# HumidityMetter.net
KiCad netlist of a schematic drawn in EAGLE
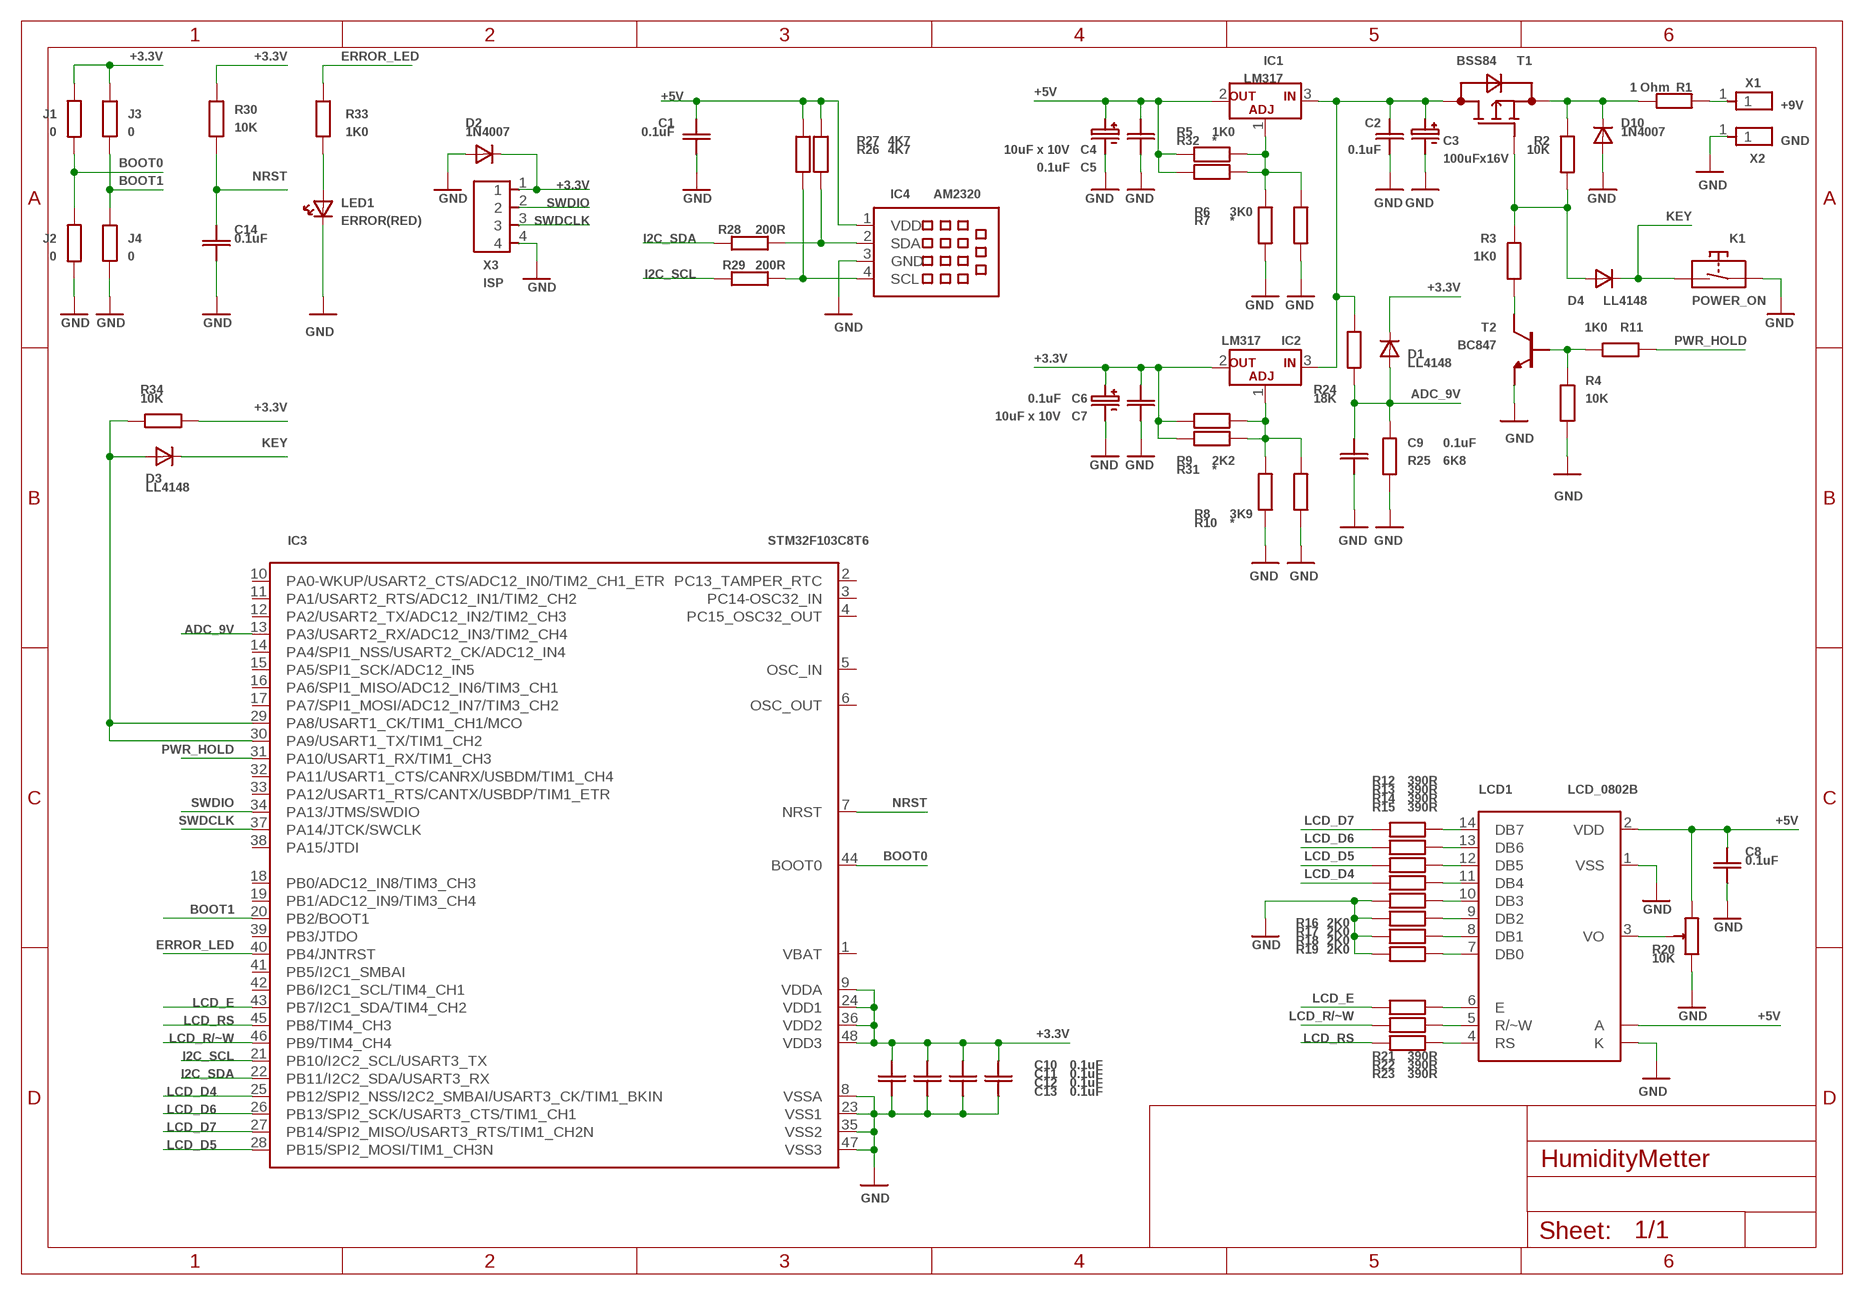
[diagram p0: schematic, sheet 1]

(export (version "E")
  (design (tool "Eeschema 10.0.6"))
  (components
    (comp (ref "C1")
      (value "0.1uF")
      (footprint "eagle-import:RSMD_0805")
      (libsource (lib "eagle-import") (part "CSMD_0805"))
    )
    (comp (ref "C2")
      (value "0.1uF")
      (footprint "eagle-import:RSMD_0805")
      (libsource (lib "eagle-import") (part "CSMD_0805"))
    )
    (comp (ref "C3")
      (value "100uFx16V")
      (footprint "eagle-import:CE_6.3MM")
      (libsource (lib "eagle-import") (part "CE6.3MM"))
    )
    (comp (ref "C4")
      (value "10uF x 10V")
      (footprint "eagle-import:CE_5.2MM")
      (libsource (lib "eagle-import") (part "CE5.2MM"))
    )
    (comp (ref "C5")
      (value "0.1uF")
      (footprint "eagle-import:RSMD_0805")
      (libsource (lib "eagle-import") (part "CSMD_0805"))
    )
    (comp (ref "C6")
      (value "0.1uF")
      (footprint "eagle-import:RSMD_0805")
      (libsource (lib "eagle-import") (part "CSMD_0805"))
    )
    (comp (ref "C7")
      (value "10uF x 10V")
      (footprint "eagle-import:CE_5.2MM")
      (libsource (lib "eagle-import") (part "CE5.2MM"))
    )
    (comp (ref "C8")
      (value "0.1uF")
      (footprint "eagle-import:RSMD_0805")
      (libsource (lib "eagle-import") (part "CSMD_0805"))
    )
    (comp (ref "C9")
      (value "0.1uF")
      (footprint "eagle-import:RSMD_0805")
      (libsource (lib "eagle-import") (part "CSMD_0805"))
    )
    (comp (ref "C10")
      (value "0.1uF")
      (footprint "eagle-import:RSMD_0805")
      (libsource (lib "eagle-import") (part "CSMD_0805"))
    )
    (comp (ref "C11")
      (value "0.1uF")
      (footprint "eagle-import:RSMD_0805")
      (libsource (lib "eagle-import") (part "CSMD_0805"))
    )
    (comp (ref "C12")
      (value "0.1uF")
      (footprint "eagle-import:RSMD_0805")
      (libsource (lib "eagle-import") (part "CSMD_0805"))
    )
    (comp (ref "C13")
      (value "0.1uF")
      (footprint "eagle-import:RSMD_0805")
      (libsource (lib "eagle-import") (part "CSMD_0805"))
    )
    (comp (ref "C14")
      (value "0.1uF")
      (footprint "eagle-import:RSMD_0805")
      (libsource (lib "eagle-import") (part "CSMD_0805"))
    )
    (comp (ref "D1")
      (value "LL4148")
      (footprint "eagle-import:SOD-80")
      (libsource (lib "eagle-import") (part "LL4147SOD-80"))
    )
    (comp (ref "D2")
      (value "1N4007")
      (footprint "eagle-import:DO-41_10MM")
      (libsource (lib "eagle-import") (part "1N4001DO-41_10MM"))
    )
    (comp (ref "D3")
      (value "LL4148")
      (footprint "eagle-import:SOD-80")
      (libsource (lib "eagle-import") (part "LL4147SOD-80"))
    )
    (comp (ref "D4")
      (value "LL4148")
      (footprint "eagle-import:SOD-80")
      (libsource (lib "eagle-import") (part "LL4147SOD-80"))
    )
    (comp (ref "D10")
      (value "1N4007")
      (footprint "eagle-import:DO-41_10MM")
      (libsource (lib "eagle-import") (part "1N4001DO-41_10MM"))
    )
    (comp (ref "IC1")
      (value "LM317")
      (footprint "eagle-import:D2PAK")
      (libsource (lib "eagle-import") (part "LM317(D2PAK)"))
    )
    (comp (ref "IC2")
      (value "LM317")
      (footprint "eagle-import:D2PAK")
      (libsource (lib "eagle-import") (part "LM317(D2PAK)"))
    )
    (comp (ref "IC3")
      (value "STM32F103C8T6")
      (footprint "eagle-import:LQFP48")
      (libsource (lib "eagle-import") (part "STM32F103C8T6(LQFP48)(LQFP48)"))
    )
    (comp (ref "IC4")
      (value "AM2320")
      (footprint "eagle-import:AM2320_HOR")
      (libsource (lib "eagle-import") (part "AM2320(HOR)"))
    )
    (comp (ref "J1")
      (value "0")
      (footprint "eagle-import:RSMD_0805")
      (libsource (lib "eagle-import") (part "RSMD_0805"))
    )
    (comp (ref "J2")
      (value "0")
      (footprint "eagle-import:RSMD_0805")
      (libsource (lib "eagle-import") (part "RSMD_0805"))
    )
    (comp (ref "J3")
      (value "0")
      (footprint "eagle-import:RSMD_0805")
      (libsource (lib "eagle-import") (part "RSMD_0805"))
    )
    (comp (ref "J4")
      (value "0")
      (footprint "eagle-import:RSMD_0805")
      (libsource (lib "eagle-import") (part "RSMD_0805"))
    )
    (comp (ref "K1")
      (value "POWER_ON")
      (footprint "eagle-import:KEY_7X4.5")
      (libsource (lib "eagle-import") (part "KEY(7X4.5)"))
    )
    (comp (ref "LCD1")
      (value "LCD_0802B")
      (footprint "eagle-import:LCD_0802B(CHINA_CLONE)")
      (libsource (lib "eagle-import") (part "LCD_0802B(0802B_CHINA_CLONE)"))
    )
    (comp (ref "LED1")
      (value "ERROR(RED)")
      (footprint "eagle-import:LED_0805")
      (libsource (lib "eagle-import") (part "LED3MM(SMD0805)"))
    )
    (comp (ref "R1")
      (value "1 Ohm")
      (footprint "eagle-import:R0207")
      (libsource (lib "eagle-import") (part "R0207"))
    )
    (comp (ref "R2")
      (value "10K")
      (footprint "eagle-import:RSMD_0805")
      (libsource (lib "eagle-import") (part "RSMD_0805"))
    )
    (comp (ref "R3")
      (value "1K0")
      (footprint "eagle-import:RSMD_0805")
      (libsource (lib "eagle-import") (part "RSMD_0805"))
    )
    (comp (ref "R4")
      (value "10K")
      (footprint "eagle-import:RSMD_0805")
      (libsource (lib "eagle-import") (part "RSMD_0805"))
    )
    (comp (ref "R5")
      (value "1K0")
      (footprint "eagle-import:RSMD_0805")
      (libsource (lib "eagle-import") (part "RSMD_0805"))
    )
    (comp (ref "R6")
      (value "3K0")
      (footprint "eagle-import:RSMD_0805")
      (libsource (lib "eagle-import") (part "RSMD_0805"))
    )
    (comp (ref "R7")
      (value "*")
      (footprint "eagle-import:RSMD_0805")
      (libsource (lib "eagle-import") (part "RSMD_0805"))
    )
    (comp (ref "R8")
      (value "3K9")
      (footprint "eagle-import:RSMD_0805")
      (libsource (lib "eagle-import") (part "RSMD_0805"))
    )
    (comp (ref "R9")
      (value "2K2")
      (footprint "eagle-import:RSMD_0805")
      (libsource (lib "eagle-import") (part "RSMD_0805"))
    )
    (comp (ref "R10")
      (value "*")
      (footprint "eagle-import:RSMD_0805")
      (libsource (lib "eagle-import") (part "RSMD_0805"))
    )
    (comp (ref "R11")
      (value "1K0")
      (footprint "eagle-import:RSMD_1206_BIG_GAP")
      (libsource (lib "eagle-import") (part "RSMD_1206_BIG_GAP"))
    )
    (comp (ref "R12")
      (value "390R")
      (footprint "eagle-import:RSMD_0805")
      (libsource (lib "eagle-import") (part "RSMD_0805"))
    )
    (comp (ref "R13")
      (value "390R")
      (footprint "eagle-import:RSMD_0805")
      (libsource (lib "eagle-import") (part "RSMD_0805"))
    )
    (comp (ref "R14")
      (value "390R")
      (footprint "eagle-import:RSMD_0805")
      (libsource (lib "eagle-import") (part "RSMD_0805"))
    )
    (comp (ref "R15")
      (value "390R")
      (footprint "eagle-import:RSMD_0805")
      (libsource (lib "eagle-import") (part "RSMD_0805"))
    )
    (comp (ref "R16")
      (value "2K0")
      (footprint "eagle-import:RSMD_0805")
      (libsource (lib "eagle-import") (part "RSMD_0805"))
    )
    (comp (ref "R17")
      (value "2K0")
      (footprint "eagle-import:RSMD_0805")
      (libsource (lib "eagle-import") (part "RSMD_0805"))
    )
    (comp (ref "R18")
      (value "2K0")
      (footprint "eagle-import:RSMD_0805")
      (libsource (lib "eagle-import") (part "RSMD_0805"))
    )
    (comp (ref "R19")
      (value "2K0")
      (footprint "eagle-import:RSMD_0805")
      (libsource (lib "eagle-import") (part "RSMD_0805"))
    )
    (comp (ref "R20")
      (value "10K")
      (footprint "eagle-import:R_ADJ_STAND")
      (libsource (lib "eagle-import") (part "R_ADJSTAND_6.5_X_3.5MM"))
    )
    (comp (ref "R21")
      (value "390R")
      (footprint "eagle-import:RSMD_0805")
      (libsource (lib "eagle-import") (part "RSMD_0805"))
    )
    (comp (ref "R22")
      (value "390R")
      (footprint "eagle-import:RSMD_0805")
      (libsource (lib "eagle-import") (part "RSMD_0805"))
    )
    (comp (ref "R23")
      (value "390R")
      (footprint "eagle-import:RSMD_0805")
      (libsource (lib "eagle-import") (part "RSMD_0805"))
    )
    (comp (ref "R24")
      (value "18K")
      (footprint "eagle-import:RSMD_1206_BIG_GAP")
      (libsource (lib "eagle-import") (part "RSMD_1206_BIG_GAP"))
    )
    (comp (ref "R25")
      (value "6K8")
      (footprint "eagle-import:RSMD_0805")
      (libsource (lib "eagle-import") (part "RSMD_0805"))
    )
    (comp (ref "R26")
      (value "4K7")
      (footprint "eagle-import:R0207")
      (libsource (lib "eagle-import") (part "R0207"))
    )
    (comp (ref "R27")
      (value "4K7")
      (footprint "eagle-import:R0207")
      (libsource (lib "eagle-import") (part "R0207"))
    )
    (comp (ref "R28")
      (value "200R")
      (footprint "eagle-import:R0207")
      (libsource (lib "eagle-import") (part "R0207"))
    )
    (comp (ref "R29")
      (value "200R")
      (footprint "eagle-import:R0207")
      (libsource (lib "eagle-import") (part "R0207"))
    )
    (comp (ref "R30")
      (value "10K")
      (footprint "eagle-import:RSMD_0805")
      (libsource (lib "eagle-import") (part "RSMD_0805"))
    )
    (comp (ref "R31")
      (value "*")
      (footprint "eagle-import:RSMD_0805")
      (libsource (lib "eagle-import") (part "RSMD_0805"))
    )
    (comp (ref "R32")
      (value "*")
      (footprint "eagle-import:RSMD_0805")
      (libsource (lib "eagle-import") (part "RSMD_0805"))
    )
    (comp (ref "R33")
      (value "1K0")
      (footprint "eagle-import:RSMD_0805")
      (libsource (lib "eagle-import") (part "RSMD_0805"))
    )
    (comp (ref "R34")
      (value "10K")
      (footprint "eagle-import:RSMD_0805")
      (libsource (lib "eagle-import") (part "RSMD_0805"))
    )
    (comp (ref "T1")
      (value "BSS84")
      (footprint "eagle-import:SOT23")
      (libsource (lib "eagle-import") (part "BSS84(SOT23)"))
    )
    (comp (ref "T2")
      (value "BC847")
      (footprint "eagle-import:SOT23_SMALL_PADS")
      (libsource (lib "eagle-import") (part "BC847SOT23_SMALL_PADS"))
    )
    (comp (ref "X1")
      (value "+9V")
      (footprint "eagle-import:PIN1X1_D3.5MM")
      (libsource (lib "eagle-import") (part "PIN1X13.5MM_DRILL"))
    )
    (comp (ref "X2")
      (value "GND")
      (footprint "eagle-import:PIN1X1_D3.5MM")
      (libsource (lib "eagle-import") (part "PIN1X13.5MM_DRILL"))
    )
    (comp (ref "X3")
      (value "ISP")
      (footprint "eagle-import:PIN4X1_2.54MM")
      (libsource (lib "eagle-import") (part "PIN4X1(2.54MM)"))
    )
  )
  (nets
    (net (code "1") (name "/+3.3V") (class "Default")
      (node (ref "C10") (pin "PAD_1") (pinfunction "PIN1_PAD_1") (pintype "bidirectional"))
      (node (ref "C11") (pin "PAD_1") (pinfunction "PIN1_PAD_1") (pintype "bidirectional"))
      (node (ref "C12") (pin "PAD_1") (pinfunction "PIN1_PAD_1") (pintype "bidirectional"))
      (node (ref "C13") (pin "PAD_1") (pinfunction "PIN1_PAD_1") (pintype "bidirectional"))
      (node (ref "C6") (pin "PAD_1") (pinfunction "PIN1_PAD_1") (pintype "bidirectional"))
      (node (ref "C7") (pin "PLUS") (pinfunction "PLUS_PLUS") (pintype "bidirectional"))
      (node (ref "D1") (pin "CATHODE") (pinfunction "CATHODE_CATHODE") (pintype "passive"))
      (node (ref "D2") (pin "CATHODE") (pinfunction "CATHODE_CATHODE") (pintype "passive"))
      (node (ref "IC2") (pin "2") (pinfunction "OUT_2") (pintype "output"))
      (node (ref "IC3") (pin "24") (pinfunction "VDD1_24") (pintype "bidirectional"))
      (node (ref "IC3") (pin "36") (pinfunction "VDD2_36") (pintype "bidirectional"))
      (node (ref "IC3") (pin "48") (pinfunction "VDD3_48") (pintype "bidirectional"))
      (node (ref "IC3") (pin "9") (pinfunction "VDDA_9") (pintype "bidirectional"))
      (node (ref "J1") (pin "PAD_0") (pinfunction "PIN0_PAD_0") (pintype "passive"))
      (node (ref "J3") (pin "PAD_0") (pinfunction "PIN0_PAD_0") (pintype "passive"))
      (node (ref "R30") (pin "PAD_0") (pinfunction "PIN0_PAD_0") (pintype "passive"))
      (node (ref "R31") (pin "PAD_1") (pinfunction "PIN1_PAD_1") (pintype "passive"))
      (node (ref "R34") (pin "PAD_1") (pinfunction "PIN1_PAD_1") (pintype "passive"))
      (node (ref "R9") (pin "PAD_1") (pinfunction "PIN1_PAD_1") (pintype "passive"))
      (node (ref "X3") (pin "1") (pinfunction "1_1") (pintype "bidirectional"))
    )
    (net (code "2") (name "/+5V") (class "Default")
      (node (ref "C1") (pin "PAD_1") (pinfunction "PIN1_PAD_1") (pintype "bidirectional"))
      (node (ref "C4") (pin "PLUS") (pinfunction "PLUS_PLUS") (pintype "bidirectional"))
      (node (ref "C5") (pin "PAD_1") (pinfunction "PIN1_PAD_1") (pintype "bidirectional"))
      (node (ref "C8") (pin "PAD_1") (pinfunction "PIN1_PAD_1") (pintype "bidirectional"))
      (node (ref "IC1") (pin "2") (pinfunction "OUT_2") (pintype "output"))
      (node (ref "IC4") (pin "1") (pinfunction "VDD_1") (pintype "bidirectional"))
      (node (ref "LCD1") (pin "2") (pinfunction "VDD_2") (pintype "bidirectional"))
      (node (ref "LCD1") (pin "A") (pinfunction "A_A") (pintype "bidirectional"))
      (node (ref "R20") (pin "3") (pinfunction "END_B_3") (pintype "passive"))
      (node (ref "R26") (pin "PAD_0") (pinfunction "PIN0_PAD_0") (pintype "passive"))
      (node (ref "R27") (pin "PAD_0") (pinfunction "PIN0_PAD_0") (pintype "passive"))
      (node (ref "R32") (pin "PAD_1") (pinfunction "PIN1_PAD_1") (pintype "passive"))
      (node (ref "R5") (pin "PAD_1") (pinfunction "PIN1_PAD_1") (pintype "passive"))
    )
    (net (code "3") (name "/ADC_9V") (class "Default")
      (node (ref "C9") (pin "PAD_1") (pinfunction "PIN1_PAD_1") (pintype "bidirectional"))
      (node (ref "D1") (pin "ANODE") (pinfunction "ANODE_ANODE") (pintype "passive"))
      (node (ref "IC3") (pin "13") (pinfunction "PA3/USART2_RX/ADC12_IN3/TIM2_CH4_13") (pintype "bidirectional"))
      (node (ref "R24") (pin "PAD_1") (pinfunction "PIN1_PAD_1") (pintype "passive"))
      (node (ref "R25") (pin "PAD_0") (pinfunction "PIN0_PAD_0") (pintype "passive"))
    )
    (net (code "4") (name "/BOOT0") (class "Default")
      (node (ref "IC3") (pin "44") (pinfunction "BOOT0_44") (pintype "bidirectional"))
      (node (ref "J1") (pin "PAD_1") (pinfunction "PIN1_PAD_1") (pintype "passive"))
      (node (ref "J2") (pin "PAD_0") (pinfunction "PIN0_PAD_0") (pintype "passive"))
    )
    (net (code "5") (name "/BOOT1") (class "Default")
      (node (ref "IC3") (pin "20") (pinfunction "PB2/BOOT1_20") (pintype "bidirectional"))
      (node (ref "J3") (pin "PAD_1") (pinfunction "PIN1_PAD_1") (pintype "passive"))
      (node (ref "J4") (pin "PAD_0") (pinfunction "PIN0_PAD_0") (pintype "passive"))
    )
    (net (code "6") (name "/ERROR_LED") (class "Default")
      (node (ref "IC3") (pin "40") (pinfunction "PB4/JNTRST_40") (pintype "bidirectional"))
      (node (ref "R33") (pin "PAD_0") (pinfunction "PIN0_PAD_0") (pintype "passive"))
    )
    (net (code "7") (name "/I2C_SCL") (class "Default")
      (node (ref "IC3") (pin "21") (pinfunction "PB10/I2C2_SCL/USART3_TX_21") (pintype "bidirectional"))
      (node (ref "R29") (pin "PAD_0") (pinfunction "PIN0_PAD_0") (pintype "passive"))
    )
    (net (code "8") (name "/I2C_SDA") (class "Default")
      (node (ref "IC3") (pin "22") (pinfunction "PB11/I2C2_SDA/USART3_RX_22") (pintype "bidirectional"))
      (node (ref "R28") (pin "PAD_0") (pinfunction "PIN0_PAD_0") (pintype "passive"))
    )
    (net (code "9") (name "/KEY") (class "Default")
      (node (ref "D3") (pin "CATHODE") (pinfunction "CATHODE_CATHODE") (pintype "passive"))
      (node (ref "D4") (pin "CATHODE") (pinfunction "CATHODE_CATHODE") (pintype "passive"))
      (node (ref "K1") (pin "3") (pinfunction "2_3") (pintype "bidirectional"))
      (node (ref "K1") (pin "4") (pinfunction "2_4") (pintype "bidirectional"))
    )
    (net (code "10") (name "/LCD_D4") (class "Default")
      (node (ref "IC3") (pin "25") (pinfunction "PB12/SPI2_NSS/I2C2_SMBAI/USART3_CK/TIM1_BKIN_25") (pintype "bidirectional"))
      (node (ref "R15") (pin "PAD_1") (pinfunction "PIN1_PAD_1") (pintype "passive"))
    )
    (net (code "11") (name "/LCD_D5") (class "Default")
      (node (ref "IC3") (pin "28") (pinfunction "PB15/SPI2_MOSI/TIM1_CH3N_28") (pintype "bidirectional"))
      (node (ref "R14") (pin "PAD_1") (pinfunction "PIN1_PAD_1") (pintype "passive"))
    )
    (net (code "12") (name "/LCD_D6") (class "Default")
      (node (ref "IC3") (pin "26") (pinfunction "PB13/SPI2_SCK/USART3_CTS/TIM1_CH1_26") (pintype "bidirectional"))
      (node (ref "R13") (pin "PAD_1") (pinfunction "PIN1_PAD_1") (pintype "passive"))
    )
    (net (code "13") (name "/LCD_D7") (class "Default")
      (node (ref "IC3") (pin "27") (pinfunction "PB14/SPI2_MISO/USART3_RTS/TIM1_CH2N_27") (pintype "bidirectional"))
      (node (ref "R12") (pin "PAD_1") (pinfunction "PIN1_PAD_1") (pintype "passive"))
    )
    (net (code "14") (name "/LCD_E") (class "Default")
      (node (ref "IC3") (pin "43") (pinfunction "PB7/I2C1_SDA/TIM4_CH2_43") (pintype "bidirectional"))
      (node (ref "R21") (pin "PAD_1") (pinfunction "PIN1_PAD_1") (pintype "passive"))
    )
    (net (code "15") (name "/LCD_RS") (class "Default")
      (node (ref "IC3") (pin "45") (pinfunction "PB8/TIM4_CH3_45") (pintype "bidirectional"))
      (node (ref "R23") (pin "PAD_1") (pinfunction "PIN1_PAD_1") (pintype "passive"))
    )
    (net (code "16") (name "/LCD_R{slash}~{W}") (class "Default")
      (node (ref "IC3") (pin "46") (pinfunction "PB9/TIM4_CH4_46") (pintype "bidirectional"))
      (node (ref "R22") (pin "PAD_1") (pinfunction "PIN1_PAD_1") (pintype "passive"))
    )
    (net (code "17") (name "/NRST") (class "Default")
      (node (ref "C14") (pin "PAD_1") (pinfunction "PIN1_PAD_1") (pintype "bidirectional"))
      (node (ref "IC3") (pin "7") (pinfunction "NRST_7") (pintype "bidirectional"))
      (node (ref "R30") (pin "PAD_1") (pinfunction "PIN1_PAD_1") (pintype "passive"))
    )
    (net (code "18") (name "/PWR_HOLD") (class "Default")
      (node (ref "IC3") (pin "31") (pinfunction "PA10/USART1_RX/TIM1_CH3_31") (pintype "bidirectional"))
      (node (ref "R11") (pin "PAD_0") (pinfunction "PIN0_PAD_0") (pintype "passive"))
    )
    (net (code "19") (name "/SWDCLK") (class "Default")
      (node (ref "IC3") (pin "37") (pinfunction "PA14/JTCK/SWCLK_37") (pintype "bidirectional"))
      (node (ref "X3") (pin "3") (pinfunction "3_3") (pintype "bidirectional"))
    )
    (net (code "20") (name "/SWDIO") (class "Default")
      (node (ref "IC3") (pin "34") (pinfunction "PA13/JTMS/SWDIO_34") (pintype "bidirectional"))
      (node (ref "X3") (pin "2") (pinfunction "2_2") (pintype "bidirectional"))
    )
    (net (code "21") (name "GND") (class "Default")
      (node (ref "C1") (pin "PAD_0") (pinfunction "PIN0_PAD_0") (pintype "bidirectional"))
      (node (ref "C10") (pin "PAD_0") (pinfunction "PIN0_PAD_0") (pintype "bidirectional"))
      (node (ref "C11") (pin "PAD_0") (pinfunction "PIN0_PAD_0") (pintype "bidirectional"))
      (node (ref "C12") (pin "PAD_0") (pinfunction "PIN0_PAD_0") (pintype "bidirectional"))
      (node (ref "C13") (pin "PAD_0") (pinfunction "PIN0_PAD_0") (pintype "bidirectional"))
      (node (ref "C14") (pin "PAD_0") (pinfunction "PIN0_PAD_0") (pintype "bidirectional"))
      (node (ref "C2") (pin "PAD_0") (pinfunction "PIN0_PAD_0") (pintype "bidirectional"))
      (node (ref "C3") (pin "MINUS") (pinfunction "MINUS_MINUS") (pintype "bidirectional"))
      (node (ref "C4") (pin "MINUS") (pinfunction "MINUS_MINUS") (pintype "bidirectional"))
      (node (ref "C5") (pin "PAD_0") (pinfunction "PIN0_PAD_0") (pintype "bidirectional"))
      (node (ref "C6") (pin "PAD_0") (pinfunction "PIN0_PAD_0") (pintype "bidirectional"))
      (node (ref "C7") (pin "MINUS") (pinfunction "MINUS_MINUS") (pintype "bidirectional"))
      (node (ref "C8") (pin "PAD_0") (pinfunction "PIN0_PAD_0") (pintype "bidirectional"))
      (node (ref "C9") (pin "PAD_0") (pinfunction "PIN0_PAD_0") (pintype "bidirectional"))
      (node (ref "D10") (pin "ANODE") (pinfunction "ANODE_ANODE") (pintype "passive"))
      (node (ref "D2") (pin "ANODE") (pinfunction "ANODE_ANODE") (pintype "passive"))
      (node (ref "IC3") (pin "23") (pinfunction "VSS1_23") (pintype "bidirectional"))
      (node (ref "IC3") (pin "35") (pinfunction "VSS2_35") (pintype "bidirectional"))
      (node (ref "IC3") (pin "47") (pinfunction "VSS3_47") (pintype "bidirectional"))
      (node (ref "IC3") (pin "8") (pinfunction "VSSA_8") (pintype "bidirectional"))
      (node (ref "IC4") (pin "3") (pinfunction "GND_3") (pintype "bidirectional"))
      (node (ref "J2") (pin "PAD_1") (pinfunction "PIN1_PAD_1") (pintype "passive"))
      (node (ref "J4") (pin "PAD_1") (pinfunction "PIN1_PAD_1") (pintype "passive"))
      (node (ref "K1") (pin "1") (pinfunction "1_1") (pintype "bidirectional"))
      (node (ref "K1") (pin "2") (pinfunction "1_2") (pintype "bidirectional"))
      (node (ref "LCD1") (pin "1") (pinfunction "VSS_1") (pintype "bidirectional"))
      (node (ref "LCD1") (pin "K") (pinfunction "K_K") (pintype "bidirectional"))
      (node (ref "LED1") (pin "CATHODE") (pinfunction "CATHODE_CATHODE") (pintype "passive"))
      (node (ref "R10") (pin "PAD_1") (pinfunction "PIN1_PAD_1") (pintype "passive"))
      (node (ref "R16") (pin "PAD_1") (pinfunction "PIN1_PAD_1") (pintype "passive"))
      (node (ref "R17") (pin "PAD_1") (pinfunction "PIN1_PAD_1") (pintype "passive"))
      (node (ref "R18") (pin "PAD_1") (pinfunction "PIN1_PAD_1") (pintype "passive"))
      (node (ref "R19") (pin "PAD_1") (pinfunction "PIN1_PAD_1") (pintype "passive"))
      (node (ref "R20") (pin "1") (pinfunction "END_A_1") (pintype "passive"))
      (node (ref "R25") (pin "PAD_1") (pinfunction "PIN1_PAD_1") (pintype "passive"))
      (node (ref "R4") (pin "PAD_1") (pinfunction "PIN1_PAD_1") (pintype "passive"))
      (node (ref "R6") (pin "PAD_1") (pinfunction "PIN1_PAD_1") (pintype "passive"))
      (node (ref "R7") (pin "PAD_1") (pinfunction "PIN1_PAD_1") (pintype "passive"))
      (node (ref "R8") (pin "PAD_1") (pinfunction "PIN1_PAD_1") (pintype "passive"))
      (node (ref "T2") (pin "2") (pinfunction "E_2") (pintype "bidirectional"))
      (node (ref "X2") (pin "1") (pinfunction "1_1") (pintype "bidirectional"))
      (node (ref "X3") (pin "4") (pinfunction "4_4") (pintype "bidirectional"))
    )
    (net (code "22") (name "Net-(C2-PIN1)") (class "Default")
      (node (ref "C2") (pin "PAD_1") (pinfunction "PIN1_PAD_1") (pintype "bidirectional"))
      (node (ref "C3") (pin "PLUS") (pinfunction "PLUS_PLUS") (pintype "bidirectional"))
      (node (ref "IC1") (pin "3") (pinfunction "IN_3") (pintype "input"))
      (node (ref "IC2") (pin "3") (pinfunction "IN_3") (pintype "input"))
      (node (ref "R24") (pin "PAD_0") (pinfunction "PIN0_PAD_0") (pintype "passive"))
      (node (ref "T1") (pin "3") (pinfunction "DRAIN_3") (pintype "bidirectional"))
    )
    (net (code "23") (name "Net-(IC1-ADJ)") (class "Default")
      (node (ref "IC1") (pin "1") (pinfunction "ADJ_1") (pintype "input"))
      (node (ref "R32") (pin "PAD_0") (pinfunction "PIN0_PAD_0") (pintype "passive"))
      (node (ref "R5") (pin "PAD_0") (pinfunction "PIN0_PAD_0") (pintype "passive"))
      (node (ref "R6") (pin "PAD_0") (pinfunction "PIN0_PAD_0") (pintype "passive"))
      (node (ref "R7") (pin "PAD_0") (pinfunction "PIN0_PAD_0") (pintype "passive"))
    )
    (net (code "24") (name "Net-(IC2-ADJ)") (class "Default")
      (node (ref "IC2") (pin "1") (pinfunction "ADJ_1") (pintype "input"))
      (node (ref "R10") (pin "PAD_0") (pinfunction "PIN0_PAD_0") (pintype "passive"))
      (node (ref "R31") (pin "PAD_0") (pinfunction "PIN0_PAD_0") (pintype "passive"))
      (node (ref "R8") (pin "PAD_0") (pinfunction "PIN0_PAD_0") (pintype "passive"))
      (node (ref "R9") (pin "PAD_0") (pinfunction "PIN0_PAD_0") (pintype "passive"))
    )
    (net (code "25") (name "Net-(IC3-PA8{slash}USART1_CK{slash}TIM1_CH1{slash}MCO)") (class "Default")
      (node (ref "D3") (pin "ANODE") (pinfunction "ANODE_ANODE") (pintype "passive"))
      (node (ref "IC3") (pin "29") (pinfunction "PA8/USART1_CK/TIM1_CH1/MCO_29") (pintype "bidirectional"))
      (node (ref "IC3") (pin "30") (pinfunction "PA9/USART1_TX/TIM1_CH2_30") (pintype "bidirectional"))
      (node (ref "R34") (pin "PAD_0") (pinfunction "PIN0_PAD_0") (pintype "passive"))
    )
    (net (code "26") (name "Net-(IC4-SCL)") (class "Default")
      (node (ref "IC4") (pin "4") (pinfunction "SCL_4") (pintype "bidirectional"))
      (node (ref "R27") (pin "PAD1") (pinfunction "PIN1_PAD1") (pintype "passive"))
      (node (ref "R29") (pin "PAD1") (pinfunction "PIN1_PAD1") (pintype "passive"))
    )
    (net (code "27") (name "Net-(IC4-SDA)") (class "Default")
      (node (ref "IC4") (pin "2") (pinfunction "SDA_2") (pintype "bidirectional"))
      (node (ref "R26") (pin "PAD1") (pinfunction "PIN1_PAD1") (pintype "passive"))
      (node (ref "R28") (pin "PAD1") (pinfunction "PIN1_PAD1") (pintype "passive"))
    )
    (net (code "28") (name "Net-(LCD1-DB0)") (class "Default")
      (node (ref "LCD1") (pin "7") (pinfunction "DB0_7") (pintype "bidirectional"))
      (node (ref "R19") (pin "PAD_0") (pinfunction "PIN0_PAD_0") (pintype "passive"))
    )
    (net (code "29") (name "Net-(LCD1-DB1)") (class "Default")
      (node (ref "LCD1") (pin "8") (pinfunction "DB1_8") (pintype "bidirectional"))
      (node (ref "R18") (pin "PAD_0") (pinfunction "PIN0_PAD_0") (pintype "passive"))
    )
    (net (code "30") (name "Net-(LCD1-DB2)") (class "Default")
      (node (ref "LCD1") (pin "9") (pinfunction "DB2_9") (pintype "bidirectional"))
      (node (ref "R17") (pin "PAD_0") (pinfunction "PIN0_PAD_0") (pintype "passive"))
    )
    (net (code "31") (name "Net-(LCD1-DB3)") (class "Default")
      (node (ref "LCD1") (pin "10") (pinfunction "DB3_10") (pintype "bidirectional"))
      (node (ref "R16") (pin "PAD_0") (pinfunction "PIN0_PAD_0") (pintype "passive"))
    )
    (net (code "32") (name "Net-(LCD1-DB4)") (class "Default")
      (node (ref "LCD1") (pin "11") (pinfunction "DB4_11") (pintype "bidirectional"))
      (node (ref "R15") (pin "PAD_0") (pinfunction "PIN0_PAD_0") (pintype "passive"))
    )
    (net (code "33") (name "Net-(LCD1-DB5)") (class "Default")
      (node (ref "LCD1") (pin "12") (pinfunction "DB5_12") (pintype "bidirectional"))
      (node (ref "R14") (pin "PAD_0") (pinfunction "PIN0_PAD_0") (pintype "passive"))
    )
    (net (code "34") (name "Net-(LCD1-DB6)") (class "Default")
      (node (ref "LCD1") (pin "13") (pinfunction "DB6_13") (pintype "bidirectional"))
      (node (ref "R13") (pin "PAD_0") (pinfunction "PIN0_PAD_0") (pintype "passive"))
    )
    (net (code "35") (name "Net-(LCD1-DB7)") (class "Default")
      (node (ref "LCD1") (pin "14") (pinfunction "DB7_14") (pintype "bidirectional"))
      (node (ref "R12") (pin "PAD_0") (pinfunction "PIN0_PAD_0") (pintype "passive"))
    )
    (net (code "36") (name "Net-(LCD1-E)") (class "Default")
      (node (ref "LCD1") (pin "6") (pinfunction "E_6") (pintype "bidirectional"))
      (node (ref "R21") (pin "PAD_0") (pinfunction "PIN0_PAD_0") (pintype "passive"))
    )
    (net (code "37") (name "Net-(LCD1-RS)") (class "Default")
      (node (ref "LCD1") (pin "4") (pinfunction "RS_4") (pintype "bidirectional"))
      (node (ref "R23") (pin "PAD_0") (pinfunction "PIN0_PAD_0") (pintype "passive"))
    )
    (net (code "38") (name "Net-(LCD1-R{slash}~{W})") (class "Default")
      (node (ref "LCD1") (pin "5") (pinfunction "R/~{W}_5") (pintype "bidirectional"))
      (node (ref "R22") (pin "PAD_0") (pinfunction "PIN0_PAD_0") (pintype "passive"))
    )
    (net (code "39") (name "Net-(LCD1-VO)") (class "Default")
      (node (ref "LCD1") (pin "3") (pinfunction "VO_3") (pintype "bidirectional"))
      (node (ref "R20") (pin "2") (pinfunction "ADJ_2") (pintype "passive"))
    )
    (net (code "40") (name "Net-(R1-PIN0)") (class "Default")
      (node (ref "D10") (pin "CATHODE") (pinfunction "CATHODE_CATHODE") (pintype "passive"))
      (node (ref "R1") (pin "PAD_0") (pinfunction "PIN0_PAD_0") (pintype "passive"))
      (node (ref "R2") (pin "PAD_0") (pinfunction "PIN0_PAD_0") (pintype "passive"))
      (node (ref "T1") (pin "2") (pinfunction "SOURCE_2") (pintype "bidirectional"))
    )
    (net (code "41") (name "Net-(R1-PIN1)") (class "Default")
      (node (ref "R1") (pin "PAD1") (pinfunction "PIN1_PAD1") (pintype "passive"))
      (node (ref "X1") (pin "1") (pinfunction "1_1") (pintype "bidirectional"))
    )
    (net (code "42") (name "Net-(R2-PIN1)") (class "Default")
      (node (ref "D4") (pin "ANODE") (pinfunction "ANODE_ANODE") (pintype "passive"))
      (node (ref "R2") (pin "PAD_1") (pinfunction "PIN1_PAD_1") (pintype "passive"))
      (node (ref "R3") (pin "PAD_0") (pinfunction "PIN0_PAD_0") (pintype "passive"))
      (node (ref "T1") (pin "1") (pinfunction "GATE_1") (pintype "bidirectional"))
    )
    (net (code "43") (name "Net-(R3-PIN1)") (class "Default")
      (node (ref "R3") (pin "PAD_1") (pinfunction "PIN1_PAD_1") (pintype "passive"))
      (node (ref "T2") (pin "3") (pinfunction "C_3") (pintype "bidirectional"))
    )
    (net (code "44") (name "Net-(R11-PIN1)") (class "Default")
      (node (ref "R11") (pin "PAD_1") (pinfunction "PIN1_PAD_1") (pintype "passive"))
      (node (ref "R4") (pin "PAD_0") (pinfunction "PIN0_PAD_0") (pintype "passive"))
      (node (ref "T2") (pin "1") (pinfunction "B_1") (pintype "bidirectional"))
    )
    (net (code "45") (name "Net-(R33-PIN1)") (class "Default")
      (node (ref "LED1") (pin "ANODE") (pinfunction "ANODE_ANODE") (pintype "passive"))
      (node (ref "R33") (pin "PAD_1") (pinfunction "PIN1_PAD_1") (pintype "passive"))
    )
    (net (code "46") (name "unconnected-(IC3-OSC_IN-Pad5)") (class "Default")
      (node (ref "IC3") (pin "5") (pinfunction "OSC_IN_5") (pintype "bidirectional"))
    )
    (net (code "47") (name "unconnected-(IC3-OSC_OUT-Pad6)") (class "Default")
      (node (ref "IC3") (pin "6") (pinfunction "OSC_OUT_6") (pintype "bidirectional"))
    )
    (net (code "48") (name "unconnected-(IC3-PA0-WKUP{slash}USART2_CTS{slash}ADC12_IN0{slash}TIM2_CH1_ETR-Pad10)") (class "Default")
      (node (ref "IC3") (pin "10") (pinfunction "PA0-WKUP/USART2_CTS/ADC12_IN0/TIM2_CH1_ETR_10") (pintype "bidirectional"))
    )
    (net (code "49") (name "unconnected-(IC3-PA1{slash}USART2_RTS{slash}ADC12_IN1{slash}TIM2_CH2-Pad11)") (class "Default")
      (node (ref "IC3") (pin "11") (pinfunction "PA1/USART2_RTS/ADC12_IN1/TIM2_CH2_11") (pintype "bidirectional"))
    )
    (net (code "50") (name "unconnected-(IC3-PA2{slash}USART2_TX{slash}ADC12_IN2{slash}TIM2_CH3-Pad12)") (class "Default")
      (node (ref "IC3") (pin "12") (pinfunction "PA2/USART2_TX/ADC12_IN2/TIM2_CH3_12") (pintype "bidirectional"))
    )
    (net (code "51") (name "unconnected-(IC3-PA4{slash}SPI1_NSS{slash}USART2_CK{slash}ADC12_IN4-Pad14)") (class "Default")
      (node (ref "IC3") (pin "14") (pinfunction "PA4/SPI1_NSS/USART2_CK/ADC12_IN4_14") (pintype "bidirectional"))
    )
    (net (code "52") (name "unconnected-(IC3-PA5{slash}SPI1_SCK{slash}ADC12_IN5-Pad15)") (class "Default")
      (node (ref "IC3") (pin "15") (pinfunction "PA5/SPI1_SCK/ADC12_IN5_15") (pintype "bidirectional"))
    )
    (net (code "53") (name "unconnected-(IC3-PA6{slash}SPI1_MISO{slash}ADC12_IN6{slash}TIM3_CH1-Pad16)") (class "Default")
      (node (ref "IC3") (pin "16") (pinfunction "PA6/SPI1_MISO/ADC12_IN6/TIM3_CH1_16") (pintype "bidirectional"))
    )
    (net (code "54") (name "unconnected-(IC3-PA7{slash}SPI1_MOSI{slash}ADC12_IN7{slash}TIM3_CH2-Pad17)") (class "Default")
      (node (ref "IC3") (pin "17") (pinfunction "PA7/SPI1_MOSI/ADC12_IN7/TIM3_CH2_17") (pintype "bidirectional"))
    )
    (net (code "55") (name "unconnected-(IC3-PA11{slash}USART1_CTS{slash}CANRX{slash}USBDM{slash}TIM1_CH4-Pad32)") (class "Default")
      (node (ref "IC3") (pin "32") (pinfunction "PA11/USART1_CTS/CANRX/USBDM/TIM1_CH4_32") (pintype "bidirectional"))
    )
    (net (code "56") (name "unconnected-(IC3-PA12{slash}USART1_RTS{slash}CANTX{slash}USBDP{slash}TIM1_ETR-Pad33)") (class "Default")
      (node (ref "IC3") (pin "33") (pinfunction "PA12/USART1_RTS/CANTX/USBDP/TIM1_ETR_33") (pintype "bidirectional"))
    )
    (net (code "57") (name "unconnected-(IC3-PA15{slash}JTDI-Pad38)") (class "Default")
      (node (ref "IC3") (pin "38") (pinfunction "PA15/JTDI_38") (pintype "bidirectional"))
    )
    (net (code "58") (name "unconnected-(IC3-PB0{slash}ADC12_IN8{slash}TIM3_CH3-Pad18)") (class "Default")
      (node (ref "IC3") (pin "18") (pinfunction "PB0/ADC12_IN8/TIM3_CH3_18") (pintype "bidirectional"))
    )
    (net (code "59") (name "unconnected-(IC3-PB1{slash}ADC12_IN9{slash}TIM3_CH4-Pad19)") (class "Default")
      (node (ref "IC3") (pin "19") (pinfunction "PB1/ADC12_IN9/TIM3_CH4_19") (pintype "bidirectional"))
    )
    (net (code "60") (name "unconnected-(IC3-PB3{slash}JTDO-Pad39)") (class "Default")
      (node (ref "IC3") (pin "39") (pinfunction "PB3/JTDO_39") (pintype "bidirectional"))
    )
    (net (code "61") (name "unconnected-(IC3-PB5{slash}I2C1_SMBAI-Pad41)") (class "Default")
      (node (ref "IC3") (pin "41") (pinfunction "PB5/I2C1_SMBAI_41") (pintype "bidirectional"))
    )
    (net (code "62") (name "unconnected-(IC3-PB6{slash}I2C1_SCL{slash}TIM4_CH1-Pad42)") (class "Default")
      (node (ref "IC3") (pin "42") (pinfunction "PB6/I2C1_SCL/TIM4_CH1_42") (pintype "bidirectional"))
    )
    (net (code "63") (name "unconnected-(IC3-PC13_TAMPER_RTC-Pad2)") (class "Default")
      (node (ref "IC3") (pin "2") (pinfunction "PC13_TAMPER_RTC_2") (pintype "bidirectional"))
    )
    (net (code "64") (name "unconnected-(IC3-PC14-OSC32_IN-Pad3)") (class "Default")
      (node (ref "IC3") (pin "3") (pinfunction "PC14-OSC32_IN_3") (pintype "bidirectional"))
    )
    (net (code "65") (name "unconnected-(IC3-PC15_OSC32_OUT-Pad4)") (class "Default")
      (node (ref "IC3") (pin "4") (pinfunction "PC15_OSC32_OUT_4") (pintype "bidirectional"))
    )
    (net (code "66") (name "unconnected-(IC3-VBAT-Pad1)") (class "Default")
      (node (ref "IC3") (pin "1") (pinfunction "VBAT_1") (pintype "bidirectional"))
    )
  )
)
